# fsr_endstop_small_mod0_1.net
KiCad netlist of a schematic drawn in EAGLE
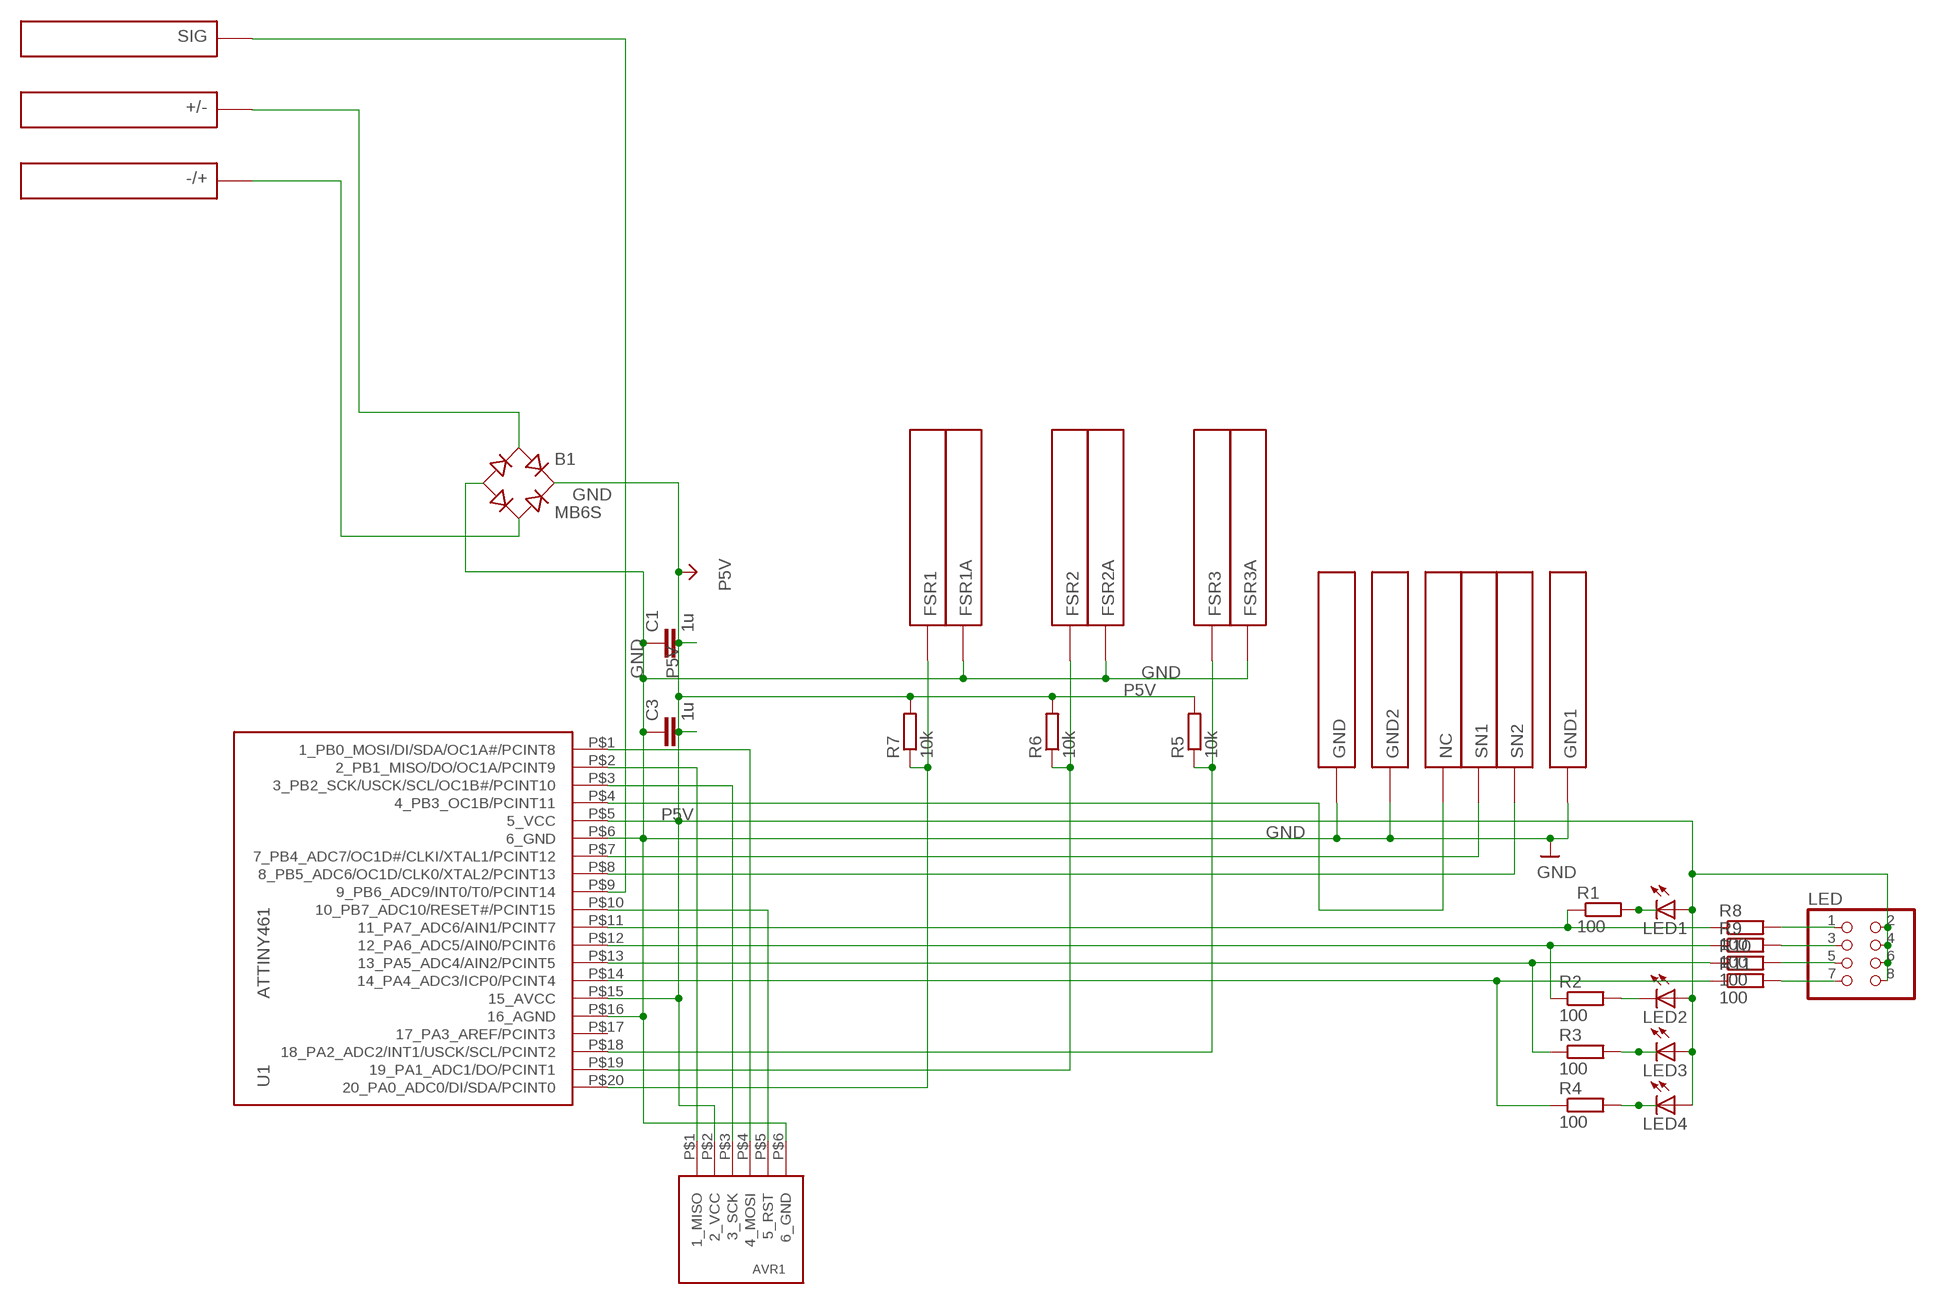
[diagram p0: schematic, sheet 1]

(export (version "E")
  (design (tool "Eeschema 10.0.6"))
  (components
    (comp (ref "+/-")
      (value "PIN1.2MM")
      (footprint "eagle-import:PIN_1.2MM")
      (libsource (lib "eagle-import") (part "PIN1.2MM"))
    )
    (comp (ref "-/+")
      (value "PIN1.2MM")
      (footprint "eagle-import:PIN_1.2MM")
      (libsource (lib "eagle-import") (part "PIN1.2MM"))
    )
    (comp (ref "AVR1")
      (value "AVR6")
      (footprint "eagle-import:AVR6")
      (libsource (lib "eagle-import") (part "AVR6"))
    )
    (comp (ref "B1")
      (value "MB6S")
      (footprint "eagle-import:SOIC-4")
      (libsource (lib "eagle-import") (part "MBS6"))
    )
    (comp (ref "C1")
      (value "1u")
      (footprint "eagle-import:C0805")
      (libsource (lib "eagle-import") (part "C-EUC0805"))
    )
    (comp (ref "C3")
      (value "1u")
      (footprint "eagle-import:C0805")
      (libsource (lib "eagle-import") (part "C-EUC0805"))
    )
    (comp (ref "FSR1")
      (value "PIN1.2MM")
      (footprint "eagle-import:PIN_1.2MM")
      (libsource (lib "eagle-import") (part "PIN1.2MM"))
    )
    (comp (ref "FSR1A")
      (value "PIN1.2MM")
      (footprint "eagle-import:PIN_1.2MM")
      (libsource (lib "eagle-import") (part "PIN1.2MM"))
    )
    (comp (ref "FSR2")
      (value "PIN1.2MM")
      (footprint "eagle-import:PIN_1.2MM")
      (libsource (lib "eagle-import") (part "PIN1.2MM"))
    )
    (comp (ref "FSR2A")
      (value "PIN1.2MM")
      (footprint "eagle-import:PIN_1.2MM")
      (libsource (lib "eagle-import") (part "PIN1.2MM"))
    )
    (comp (ref "FSR3")
      (value "PIN1.2MM")
      (footprint "eagle-import:PIN_1.2MM")
      (libsource (lib "eagle-import") (part "PIN1.2MM"))
    )
    (comp (ref "FSR3A")
      (value "PIN1.2MM")
      (footprint "eagle-import:PIN_1.2MM")
      (libsource (lib "eagle-import") (part "PIN1.2MM"))
    )
    (comp (ref "GND")
      (value "PIN1.2MM")
      (footprint "eagle-import:PIN_1.2MM")
      (libsource (lib "eagle-import") (part "PIN1.2MM"))
    )
    (comp (ref "GND1")
      (value "PIN1.2MM")
      (footprint "eagle-import:PIN_1.2MM")
      (libsource (lib "eagle-import") (part "PIN1.2MM"))
    )
    (comp (ref "GND2")
      (value "PIN1.2MM")
      (footprint "eagle-import:PIN_1.2MM")
      (libsource (lib "eagle-import") (part "PIN1.2MM"))
    )
    (comp (ref "LED")
      (value "PINHD-2X4")
      (footprint "eagle-import:2X04")
      (libsource (lib "eagle-import") (part "PINHD-2X4"))
    )
    (comp (ref "LED1")
      (value "LEDCHIP-LED0805")
      (footprint "eagle-import:CHIP-LED0805")
      (libsource (lib "eagle-import") (part "LEDCHIP-LED0805"))
    )
    (comp (ref "LED2")
      (value "LEDCHIP-LED0805")
      (footprint "eagle-import:CHIP-LED0805")
      (libsource (lib "eagle-import") (part "LEDCHIP-LED0805"))
    )
    (comp (ref "LED3")
      (value "LEDCHIP-LED0805")
      (footprint "eagle-import:CHIP-LED0805")
      (libsource (lib "eagle-import") (part "LEDCHIP-LED0805"))
    )
    (comp (ref "LED4")
      (value "LEDCHIP-LED0805")
      (footprint "eagle-import:CHIP-LED0805")
      (libsource (lib "eagle-import") (part "LEDCHIP-LED0805"))
    )
    (comp (ref "NC")
      (value "PIN1.2MM")
      (footprint "eagle-import:PIN_1.2MM")
      (libsource (lib "eagle-import") (part "PIN1.2MM"))
    )
    (comp (ref "R1")
      (value "100")
      (footprint "eagle-import:R0805")
      (libsource (lib "eagle-import") (part "R-EU_R0805"))
    )
    (comp (ref "R2")
      (value "100")
      (footprint "eagle-import:R0805")
      (libsource (lib "eagle-import") (part "R-EU_R0805"))
    )
    (comp (ref "R3")
      (value "100")
      (footprint "eagle-import:R0805")
      (libsource (lib "eagle-import") (part "R-EU_R0805"))
    )
    (comp (ref "R4")
      (value "100")
      (footprint "eagle-import:R0805")
      (libsource (lib "eagle-import") (part "R-EU_R0805"))
    )
    (comp (ref "R5")
      (value "10k")
      (footprint "eagle-import:R0805")
      (libsource (lib "eagle-import") (part "R-EU_R0805"))
    )
    (comp (ref "R6")
      (value "10k")
      (footprint "eagle-import:R0805")
      (libsource (lib "eagle-import") (part "R-EU_R0805"))
    )
    (comp (ref "R7")
      (value "10k")
      (footprint "eagle-import:R0805")
      (libsource (lib "eagle-import") (part "R-EU_R0805"))
    )
    (comp (ref "R8")
      (value "100")
      (footprint "eagle-import:R0805")
      (libsource (lib "eagle-import") (part "R-EU_R0805"))
    )
    (comp (ref "R9")
      (value "100")
      (footprint "eagle-import:R0805")
      (libsource (lib "eagle-import") (part "R-EU_R0805"))
    )
    (comp (ref "R10")
      (value "100")
      (footprint "eagle-import:R0805")
      (libsource (lib "eagle-import") (part "R-EU_R0805"))
    )
    (comp (ref "R11")
      (value "100")
      (footprint "eagle-import:R0805")
      (libsource (lib "eagle-import") (part "R-EU_R0805"))
    )
    (comp (ref "SIG")
      (value "PIN1.2MM")
      (footprint "eagle-import:PIN_1.2MM")
      (libsource (lib "eagle-import") (part "PIN1.2MM"))
    )
    (comp (ref "SN1")
      (value "PIN1.2MM")
      (footprint "eagle-import:PIN_1.2MM")
      (libsource (lib "eagle-import") (part "PIN1.2MM"))
    )
    (comp (ref "SN2")
      (value "PIN1.2MM")
      (footprint "eagle-import:PIN_1.2MM")
      (libsource (lib "eagle-import") (part "PIN1.2MM"))
    )
    (comp (ref "U1")
      (value "ATTINY461")
      (footprint "eagle-import:SOIC-20")
      (libsource (lib "eagle-import") (part "ATTINY461"))
    )
  )
  (nets
    (net (code "1") (name "GND") (class "Default")
      (node (ref "AVR1") (pin "P$6") (pinfunction "6_GND_P$6") (pintype "bidirectional"))
      (node (ref "B1") (pin "-") (pinfunction "-_-") (pintype "passive"))
      (node (ref "C1") (pin "1") (pinfunction "1_1") (pintype "passive"))
      (node (ref "C3") (pin "1") (pinfunction "1_1") (pintype "passive"))
      (node (ref "FSR1A") (pin "P$1") (pinfunction "P$1_P$1") (pintype "bidirectional"))
      (node (ref "FSR2A") (pin "P$1") (pinfunction "P$1_P$1") (pintype "bidirectional"))
      (node (ref "FSR3A") (pin "P$1") (pinfunction "P$1_P$1") (pintype "bidirectional"))
      (node (ref "GND") (pin "P$1") (pinfunction "P$1_P$1") (pintype "bidirectional"))
      (node (ref "GND1") (pin "P$1") (pinfunction "P$1_P$1") (pintype "bidirectional"))
      (node (ref "GND2") (pin "P$1") (pinfunction "P$1_P$1") (pintype "bidirectional"))
      (node (ref "U1") (pin "P$16") (pinfunction "16_AGND_P$16") (pintype "bidirectional"))
      (node (ref "U1") (pin "P$6") (pinfunction "6_GND_P$6") (pintype "bidirectional"))
    )
    (net (code "2") (name "Net-(AVR1-1_MISO)") (class "Default")
      (node (ref "AVR1") (pin "P$1") (pinfunction "1_MISO_P$1") (pintype "bidirectional"))
      (node (ref "U1") (pin "P$2") (pinfunction "2_PB1_MISO/DO/OC1A/PCINT9_P$2") (pintype "bidirectional"))
    )
    (net (code "3") (name "Net-(AVR1-3_SCK)") (class "Default")
      (node (ref "AVR1") (pin "P$3") (pinfunction "3_SCK_P$3") (pintype "bidirectional"))
      (node (ref "U1") (pin "P$3") (pinfunction "3_PB2_SCK/USCK/SCL/OC1B#/PCINT10_P$3") (pintype "bidirectional"))
    )
    (net (code "4") (name "Net-(AVR1-4_MOSI)") (class "Default")
      (node (ref "AVR1") (pin "P$4") (pinfunction "4_MOSI_P$4") (pintype "bidirectional"))
      (node (ref "U1") (pin "P$1") (pinfunction "1_PB0_MOSI/DI/SDA/OC1A#/PCINT8_P$1") (pintype "bidirectional"))
    )
    (net (code "5") (name "Net-(AVR1-5_RST)") (class "Default")
      (node (ref "AVR1") (pin "P$5") (pinfunction "5_RST_P$5") (pintype "bidirectional"))
      (node (ref "U1") (pin "P$10") (pinfunction "10_PB7_ADC10/RESET#/PCINT15_P$10") (pintype "bidirectional"))
    )
    (net (code "6") (name "Net-(B1-AC1)") (class "Default")
      (node (ref "+/-") (pin "P$1") (pinfunction "P$1_P$1") (pintype "bidirectional"))
      (node (ref "B1") (pin "~1") (pinfunction "AC1_~1") (pintype "passive"))
    )
    (net (code "7") (name "Net-(B1-AC2)") (class "Default")
      (node (ref "-/+") (pin "P$1") (pinfunction "P$1_P$1") (pintype "bidirectional"))
      (node (ref "B1") (pin "~2") (pinfunction "AC2_~2") (pintype "passive"))
    )
    (net (code "8") (name "Net-(LED-Pad1)") (class "Default")
      (node (ref "LED") (pin "1") (pinfunction "1_1") (pintype "passive"))
      (node (ref "R8") (pin "2") (pinfunction "2_2") (pintype "passive"))
    )
    (net (code "9") (name "Net-(LED-Pad3)") (class "Default")
      (node (ref "LED") (pin "3") (pinfunction "3_3") (pintype "passive"))
      (node (ref "R9") (pin "2") (pinfunction "2_2") (pintype "passive"))
    )
    (net (code "10") (name "Net-(LED-Pad5)") (class "Default")
      (node (ref "LED") (pin "5") (pinfunction "5_5") (pintype "passive"))
      (node (ref "R10") (pin "2") (pinfunction "2_2") (pintype "passive"))
    )
    (net (code "11") (name "Net-(LED-Pad7)") (class "Default")
      (node (ref "LED") (pin "7") (pinfunction "7_7") (pintype "passive"))
      (node (ref "R11") (pin "2") (pinfunction "2_2") (pintype "passive"))
    )
    (net (code "12") (name "Net-(LED1-PadC)") (class "Default")
      (node (ref "LED1") (pin "C") (pinfunction "C_C") (pintype "passive"))
      (node (ref "R1") (pin "2") (pinfunction "2_2") (pintype "passive"))
    )
    (net (code "13") (name "Net-(LED2-PadC)") (class "Default")
      (node (ref "LED2") (pin "C") (pinfunction "C_C") (pintype "passive"))
      (node (ref "R2") (pin "2") (pinfunction "2_2") (pintype "passive"))
    )
    (net (code "14") (name "Net-(LED3-PadC)") (class "Default")
      (node (ref "LED3") (pin "C") (pinfunction "C_C") (pintype "passive"))
      (node (ref "R3") (pin "2") (pinfunction "2_2") (pintype "passive"))
    )
    (net (code "15") (name "Net-(LED4-PadC)") (class "Default")
      (node (ref "LED4") (pin "C") (pinfunction "C_C") (pintype "passive"))
      (node (ref "R4") (pin "2") (pinfunction "2_2") (pintype "passive"))
    )
    (net (code "16") (name "Net-(U1-4_PB3_OC1B{slash}PCINT11)") (class "Default")
      (node (ref "NC") (pin "P$1") (pinfunction "P$1_P$1") (pintype "bidirectional"))
      (node (ref "U1") (pin "P$4") (pinfunction "4_PB3_OC1B/PCINT11_P$4") (pintype "bidirectional"))
    )
    (net (code "17") (name "Net-(U1-7_PB4_ADC7{slash}OC1D#{slash}CLKI{slash}XTAL1{slash}PCINT12)") (class "Default")
      (node (ref "SN1") (pin "P$1") (pinfunction "P$1_P$1") (pintype "bidirectional"))
      (node (ref "U1") (pin "P$7") (pinfunction "7_PB4_ADC7/OC1D#/CLKI/XTAL1/PCINT12_P$7") (pintype "bidirectional"))
    )
    (net (code "18") (name "Net-(U1-8_PB5_ADC6{slash}OC1D{slash}CLK0{slash}XTAL2{slash}PCINT13)") (class "Default")
      (node (ref "SN2") (pin "P$1") (pinfunction "P$1_P$1") (pintype "bidirectional"))
      (node (ref "U1") (pin "P$8") (pinfunction "8_PB5_ADC6/OC1D/CLK0/XTAL2/PCINT13_P$8") (pintype "bidirectional"))
    )
    (net (code "19") (name "Net-(U1-9_PB6_ADC9{slash}INT0{slash}T0{slash}PCINT14)") (class "Default")
      (node (ref "SIG") (pin "P$1") (pinfunction "P$1_P$1") (pintype "bidirectional"))
      (node (ref "U1") (pin "P$9") (pinfunction "9_PB6_ADC9/INT0/T0/PCINT14_P$9") (pintype "bidirectional"))
    )
    (net (code "20") (name "Net-(U1-11_PA7_ADC6{slash}AIN1{slash}PCINT7)") (class "Default")
      (node (ref "R1") (pin "1") (pinfunction "1_1") (pintype "passive"))
      (node (ref "R8") (pin "1") (pinfunction "1_1") (pintype "passive"))
      (node (ref "U1") (pin "P$11") (pinfunction "11_PA7_ADC6/AIN1/PCINT7_P$11") (pintype "bidirectional"))
    )
    (net (code "21") (name "Net-(U1-12_PA6_ADC5{slash}AIN0{slash}PCINT6)") (class "Default")
      (node (ref "R2") (pin "1") (pinfunction "1_1") (pintype "passive"))
      (node (ref "R9") (pin "1") (pinfunction "1_1") (pintype "passive"))
      (node (ref "U1") (pin "P$12") (pinfunction "12_PA6_ADC5/AIN0/PCINT6_P$12") (pintype "bidirectional"))
    )
    (net (code "22") (name "Net-(U1-13_PA5_ADC4{slash}AIN2{slash}PCINT5)") (class "Default")
      (node (ref "R10") (pin "1") (pinfunction "1_1") (pintype "passive"))
      (node (ref "R3") (pin "1") (pinfunction "1_1") (pintype "passive"))
      (node (ref "U1") (pin "P$13") (pinfunction "13_PA5_ADC4/AIN2/PCINT5_P$13") (pintype "bidirectional"))
    )
    (net (code "23") (name "Net-(U1-14_PA4_ADC3{slash}ICP0{slash}PCINT4)") (class "Default")
      (node (ref "R11") (pin "1") (pinfunction "1_1") (pintype "passive"))
      (node (ref "R4") (pin "1") (pinfunction "1_1") (pintype "passive"))
      (node (ref "U1") (pin "P$14") (pinfunction "14_PA4_ADC3/ICP0/PCINT4_P$14") (pintype "bidirectional"))
    )
    (net (code "24") (name "Net-(U1-18_PA2_ADC2{slash}INT1{slash}USCK{slash}SCL{slash}PCINT2)") (class "Default")
      (node (ref "FSR3") (pin "P$1") (pinfunction "P$1_P$1") (pintype "bidirectional"))
      (node (ref "R5") (pin "1") (pinfunction "1_1") (pintype "passive"))
      (node (ref "U1") (pin "P$18") (pinfunction "18_PA2_ADC2/INT1/USCK/SCL/PCINT2_P$18") (pintype "bidirectional"))
    )
    (net (code "25") (name "Net-(U1-19_PA1_ADC1{slash}DO{slash}PCINT1)") (class "Default")
      (node (ref "FSR2") (pin "P$1") (pinfunction "P$1_P$1") (pintype "bidirectional"))
      (node (ref "R6") (pin "1") (pinfunction "1_1") (pintype "passive"))
      (node (ref "U1") (pin "P$19") (pinfunction "19_PA1_ADC1/DO/PCINT1_P$19") (pintype "bidirectional"))
    )
    (net (code "26") (name "Net-(U1-20_PA0_ADC0{slash}DI{slash}SDA{slash}PCINT0)") (class "Default")
      (node (ref "FSR1") (pin "P$1") (pinfunction "P$1_P$1") (pintype "bidirectional"))
      (node (ref "R7") (pin "1") (pinfunction "1_1") (pintype "passive"))
      (node (ref "U1") (pin "P$20") (pinfunction "20_PA0_ADC0/DI/SDA/PCINT0_P$20") (pintype "bidirectional"))
    )
    (net (code "27") (name "P5V") (class "Default")
      (node (ref "AVR1") (pin "P$2") (pinfunction "2_VCC_P$2") (pintype "bidirectional"))
      (node (ref "B1") (pin "+") (pinfunction "+_+") (pintype "passive"))
      (node (ref "C1") (pin "2") (pinfunction "2_2") (pintype "passive"))
      (node (ref "C3") (pin "2") (pinfunction "2_2") (pintype "passive"))
      (node (ref "LED") (pin "2") (pinfunction "2_2") (pintype "passive"))
      (node (ref "LED") (pin "4") (pinfunction "4_4") (pintype "passive"))
      (node (ref "LED") (pin "6") (pinfunction "6_6") (pintype "passive"))
      (node (ref "LED") (pin "8") (pinfunction "8_8") (pintype "passive"))
      (node (ref "LED1") (pin "A") (pinfunction "A_A") (pintype "passive"))
      (node (ref "LED2") (pin "A") (pinfunction "A_A") (pintype "passive"))
      (node (ref "LED3") (pin "A") (pinfunction "A_A") (pintype "passive"))
      (node (ref "LED4") (pin "A") (pinfunction "A_A") (pintype "passive"))
      (node (ref "R5") (pin "2") (pinfunction "2_2") (pintype "passive"))
      (node (ref "R6") (pin "2") (pinfunction "2_2") (pintype "passive"))
      (node (ref "R7") (pin "2") (pinfunction "2_2") (pintype "passive"))
      (node (ref "U1") (pin "P$15") (pinfunction "15_AVCC_P$15") (pintype "bidirectional"))
      (node (ref "U1") (pin "P$5") (pinfunction "5_VCC_P$5") (pintype "bidirectional"))
    )
    (net (code "28") (name "unconnected-(U1-17_PA3_AREF{slash}PCINT3-PadP$17)") (class "Default")
      (node (ref "U1") (pin "P$17") (pinfunction "17_PA3_AREF/PCINT3_P$17") (pintype "bidirectional"))
    )
  )
)
